# Driver.net
KiCad netlist of a schematic drawn in EAGLE
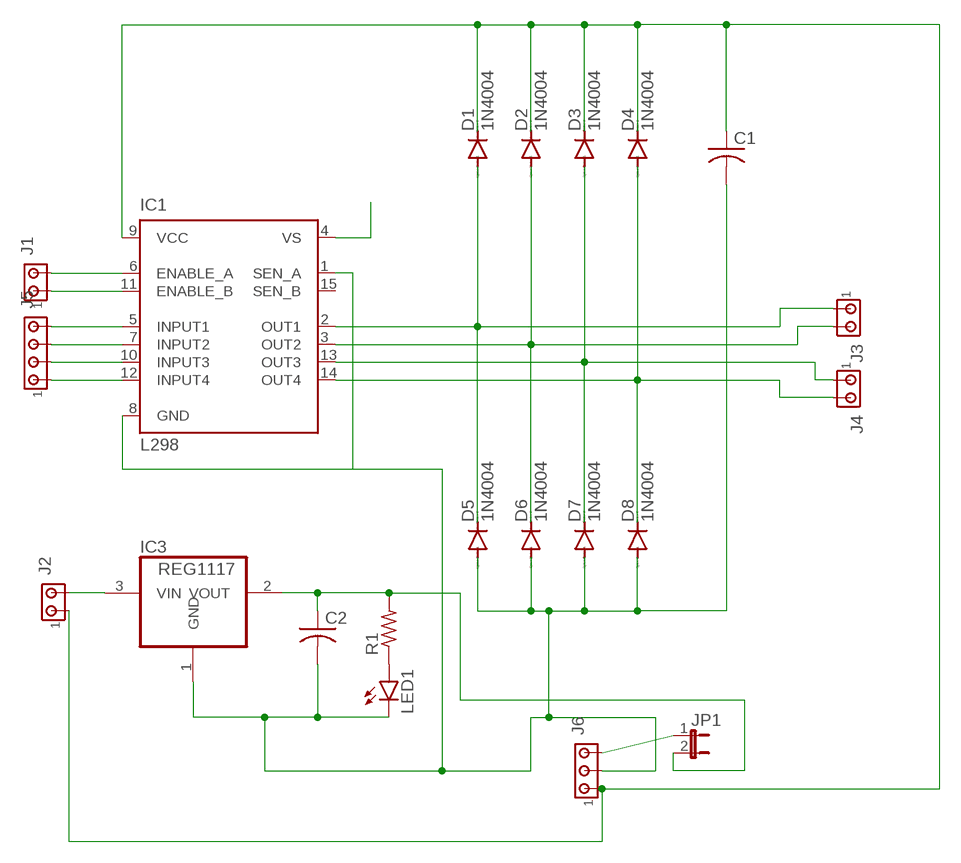
[diagram p0: schematic, sheet 1]

(export (version "E")
  (design (tool "Eeschema 10.0.6"))
  (components
    (comp (ref "C1")
      (value "C-US050-024X044")
      (footprint "eagle-import:C050-024X044")
      (libsource (lib "eagle-import") (part "C-US050-024X044"))
    )
    (comp (ref "C2")
      (value "C-US050-024X044")
      (footprint "eagle-import:C050-024X044")
      (libsource (lib "eagle-import") (part "C-US050-024X044"))
    )
    (comp (ref "D1")
      (value "1N4004")
      (footprint "eagle-import:DO41-10")
      (libsource (lib "eagle-import") (part "1N4004"))
    )
    (comp (ref "D2")
      (value "1N4004")
      (footprint "eagle-import:DO41-10")
      (libsource (lib "eagle-import") (part "1N4004"))
    )
    (comp (ref "D3")
      (value "1N4004")
      (footprint "eagle-import:DO41-10")
      (libsource (lib "eagle-import") (part "1N4004"))
    )
    (comp (ref "D4")
      (value "1N4004")
      (footprint "eagle-import:DO41-10")
      (libsource (lib "eagle-import") (part "1N4004"))
    )
    (comp (ref "D5")
      (value "1N4004")
      (footprint "eagle-import:DO41-10")
      (libsource (lib "eagle-import") (part "1N4004"))
    )
    (comp (ref "D6")
      (value "1N4004")
      (footprint "eagle-import:DO41-10")
      (libsource (lib "eagle-import") (part "1N4004"))
    )
    (comp (ref "D7")
      (value "1N4004")
      (footprint "eagle-import:DO41-10")
      (libsource (lib "eagle-import") (part "1N4004"))
    )
    (comp (ref "D8")
      (value "1N4004")
      (footprint "eagle-import:DO41-10")
      (libsource (lib "eagle-import") (part "1N4004"))
    )
    (comp (ref "IC1")
      (value "L298")
      (footprint "eagle-import:MULTIWATT-15")
      (fields (field (name "MPN") "L298N"))
      (libsource (lib "eagle-import") (part "L298"))
    )
    (comp (ref "IC3")
      (value "REG1117")
      (footprint "eagle-import:SOT223")
      (libsource (lib "eagle-import") (part "REG1117"))
    )
    (comp (ref "J1")
      (value "MTA02-156")
      (footprint "eagle-import:1X2MTA")
      (libsource (lib "eagle-import") (part "MTA02-156"))
    )
    (comp (ref "J2")
      (value "MTA02-156")
      (footprint "eagle-import:1X2MTA")
      (libsource (lib "eagle-import") (part "MTA02-156"))
    )
    (comp (ref "J3")
      (value "MTA02-156")
      (footprint "eagle-import:1X2MTA")
      (libsource (lib "eagle-import") (part "MTA02-156"))
    )
    (comp (ref "J4")
      (value "MTA02-156")
      (footprint "eagle-import:1X2MTA")
      (libsource (lib "eagle-import") (part "MTA02-156"))
    )
    (comp (ref "J5")
      (value "MTA04-156")
      (footprint "eagle-import:1X4MTA")
      (libsource (lib "eagle-import") (part "MTA04-156"))
    )
    (comp (ref "J6")
      (value "MTA03-100")
      (footprint "eagle-import:10X03MTA")
      (libsource (lib "eagle-import") (part "MTA03-100"))
    )
    (comp (ref "JP1")
      (value "JP1E")
      (footprint "eagle-import:JP1")
      (libsource (lib "eagle-import") (part "JP1E"))
    )
    (comp (ref "LED1")
      (value "LED5MM")
      (footprint "eagle-import:LED5MM")
      (libsource (lib "eagle-import") (part "LED5MM"))
    )
    (comp (ref "R1")
      (value "R-US_0207/10")
      (footprint "eagle-import:0207_10")
      (libsource (lib "eagle-import") (part "R-US_0207/10"))
    )
  )
  (nets
    (net (code "1") (name "Net-(IC1-ENABLE_A)") (class "Default")
      (node (ref "IC1") (pin "6") (pinfunction "ENABLE_A_6") (pintype "input"))
      (node (ref "J1") (pin "2") (pinfunction "2_2") (pintype "passive"))
    )
    (net (code "2") (name "Net-(IC1-ENABLE_B)") (class "Default")
      (node (ref "IC1") (pin "11") (pinfunction "ENABLE_B_11") (pintype "input"))
      (node (ref "J1") (pin "1") (pinfunction "1_1") (pintype "passive"))
    )
    (net (code "3") (name "Net-(IC1-GND)") (class "Default")
      (node (ref "C1") (pin "2") (pinfunction "2_2") (pintype "passive"))
      (node (ref "C2") (pin "2") (pinfunction "2_2") (pintype "passive"))
      (node (ref "D5") (pin "A") (pinfunction "A_A") (pintype "passive"))
      (node (ref "D6") (pin "A") (pinfunction "A_A") (pintype "passive"))
      (node (ref "D7") (pin "A") (pinfunction "A_A") (pintype "passive"))
      (node (ref "D8") (pin "A") (pinfunction "A_A") (pintype "passive"))
      (node (ref "IC1") (pin "1") (pinfunction "SEN_A_1") (pintype "input"))
      (node (ref "IC1") (pin "8") (pinfunction "GND_8") (pintype "power_in"))
      (node (ref "IC3") (pin "1") (pinfunction "GND_1") (pintype "power_in"))
      (node (ref "J6") (pin "2") (pinfunction "2_2") (pintype "passive"))
      (node (ref "LED1") (pin "K") (pinfunction "C_K") (pintype "passive"))
    )
    (net (code "4") (name "Net-(IC1-INPUT1)") (class "Default")
      (node (ref "IC1") (pin "5") (pinfunction "INPUT1_5") (pintype "input"))
      (node (ref "J5") (pin "4") (pinfunction "4_4") (pintype "passive"))
    )
    (net (code "5") (name "Net-(IC1-INPUT2)") (class "Default")
      (node (ref "IC1") (pin "7") (pinfunction "INPUT2_7") (pintype "input"))
      (node (ref "J5") (pin "3") (pinfunction "3_3") (pintype "passive"))
    )
    (net (code "6") (name "Net-(IC1-INPUT3)") (class "Default")
      (node (ref "IC1") (pin "10") (pinfunction "INPUT3_10") (pintype "input"))
      (node (ref "J5") (pin "2") (pinfunction "2_2") (pintype "passive"))
    )
    (net (code "7") (name "Net-(IC1-INPUT4)") (class "Default")
      (node (ref "IC1") (pin "12") (pinfunction "INPUT4_12") (pintype "input"))
      (node (ref "J5") (pin "1") (pinfunction "1_1") (pintype "passive"))
    )
    (net (code "8") (name "Net-(IC1-OUT1)") (class "Default")
      (node (ref "D1") (pin "A") (pinfunction "A_A") (pintype "passive"))
      (node (ref "D5") (pin "C") (pinfunction "C_C") (pintype "passive"))
      (node (ref "IC1") (pin "2") (pinfunction "OUT1_2") (pintype "output"))
      (node (ref "J3") (pin "1") (pinfunction "1_1") (pintype "passive"))
    )
    (net (code "9") (name "Net-(IC1-OUT2)") (class "Default")
      (node (ref "D2") (pin "A") (pinfunction "A_A") (pintype "passive"))
      (node (ref "D6") (pin "C") (pinfunction "C_C") (pintype "passive"))
      (node (ref "IC1") (pin "3") (pinfunction "OUT2_3") (pintype "output"))
      (node (ref "J3") (pin "2") (pinfunction "2_2") (pintype "passive"))
    )
    (net (code "10") (name "Net-(IC1-OUT3)") (class "Default")
      (node (ref "D3") (pin "A") (pinfunction "A_A") (pintype "passive"))
      (node (ref "D7") (pin "C") (pinfunction "C_C") (pintype "passive"))
      (node (ref "IC1") (pin "13") (pinfunction "OUT3_13") (pintype "output"))
      (node (ref "J4") (pin "1") (pinfunction "1_1") (pintype "passive"))
    )
    (net (code "11") (name "Net-(IC1-OUT4)") (class "Default")
      (node (ref "D4") (pin "A") (pinfunction "A_A") (pintype "passive"))
      (node (ref "D8") (pin "C") (pinfunction "C_C") (pintype "passive"))
      (node (ref "IC1") (pin "14") (pinfunction "OUT4_14") (pintype "output"))
      (node (ref "J4") (pin "2") (pinfunction "2_2") (pintype "passive"))
    )
    (net (code "12") (name "Net-(IC1-VCC)") (class "Default")
      (node (ref "C1") (pin "1") (pinfunction "1_1") (pintype "passive"))
      (node (ref "D1") (pin "C") (pinfunction "C_C") (pintype "passive"))
      (node (ref "D2") (pin "C") (pinfunction "C_C") (pintype "passive"))
      (node (ref "D3") (pin "C") (pinfunction "C_C") (pintype "passive"))
      (node (ref "D4") (pin "C") (pinfunction "C_C") (pintype "passive"))
      (node (ref "IC1") (pin "9") (pinfunction "VCC_9") (pintype "power_in"))
      (node (ref "J2") (pin "1") (pinfunction "1_1") (pintype "passive"))
      (node (ref "J6") (pin "1") (pinfunction "1_1") (pintype "passive"))
    )
    (net (code "13") (name "Net-(IC3-VIN)") (class "Default")
      (node (ref "IC3") (pin "3") (pinfunction "VIN_3") (pintype "input"))
      (node (ref "J2") (pin "2") (pinfunction "2_2") (pintype "passive"))
    )
    (net (code "14") (name "Net-(IC3-VOUT)") (class "Default")
      (node (ref "C2") (pin "1") (pinfunction "1_1") (pintype "passive"))
      (node (ref "IC3") (pin "2") (pinfunction "VOUT_2") (pintype "output"))
      (node (ref "JP1") (pin "2") (pinfunction "2_2") (pintype "passive"))
      (node (ref "R1") (pin "2") (pinfunction "2_2") (pintype "passive"))
    )
    (net (code "15") (name "Net-(J6-Pad3)") (class "Default")
      (node (ref "J6") (pin "3") (pinfunction "3_3") (pintype "passive"))
      (node (ref "JP1") (pin "1") (pinfunction "1_1") (pintype "passive"))
    )
    (net (code "16") (name "Net-(LED1-PadA)") (class "Default")
      (node (ref "LED1") (pin "A") (pinfunction "A_A") (pintype "passive"))
      (node (ref "R1") (pin "1") (pinfunction "1_1") (pintype "passive"))
    )
    (net (code "17") (name "unconnected-(IC1-SEN_B-Pad15)") (class "Default")
      (node (ref "IC1") (pin "15") (pinfunction "SEN_B_15") (pintype "input"))
    )
    (net (code "18") (name "unconnected-(IC1-VS-Pad4)") (class "Default")
      (node (ref "IC1") (pin "4") (pinfunction "VS_4") (pintype "power_in"))
    )
  )
)
